# IQ_modulator.net
KiCad netlist of a schematic drawn in Altium Designer
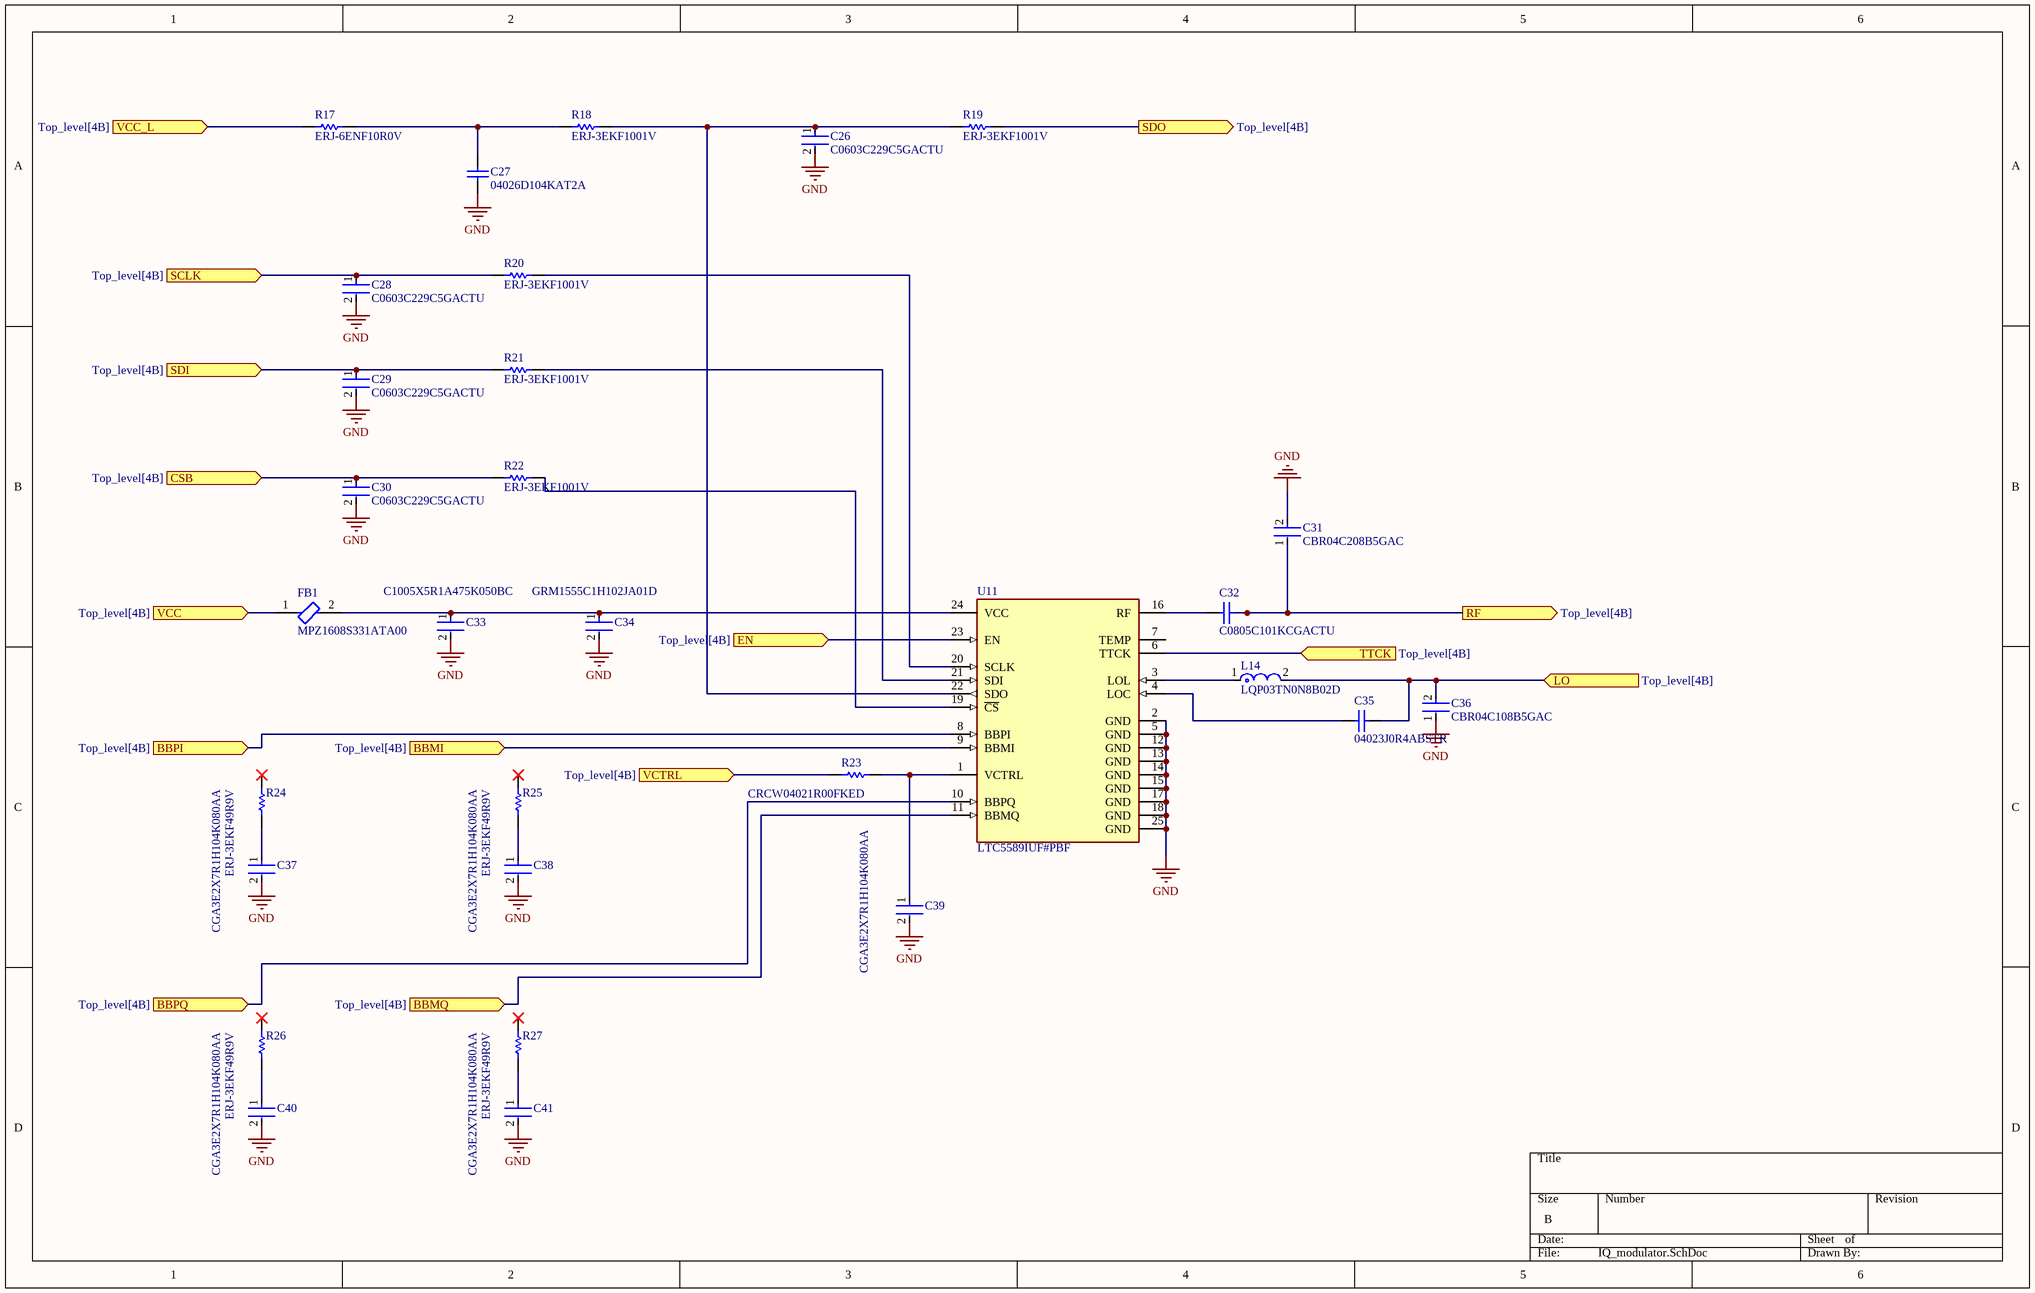
[diagram p0: IQ_modulator.SchDoc]

(export (version "E")
  (design (tool "Eeschema 10.0.6"))
  (components
    (comp (ref "C26")
      (value "C0603C229C5GACTU")
      (footprint "FP-C0603C-CF-MFG")
      (description "CAP CER 2.2PF 50V NP0 0603")
      (fields (field (name "MANUFACTURER") "KEMET") (field (name "TOLERANCE") "0.25 pF"))
      (libsource (lib "Altium Content Vault") (part "b4654b650e69147ec39a6b967a45e02"))
    )
    (comp (ref "C27")
      (value "04026D104KAT2A")
      (footprint "CAPC1005X56X25LL10T15")
      (fields (field (name "MANUFACTURER") "AVX Interconnect / Elco"))
      (libsource (lib "Altium Content Vault") (part "CAP"))
    )
    (comp (ref "C28")
      (value "C0603C229C5GACTU")
      (footprint "FP-C0603C-CF-MFG")
      (description "CAP CER 2.2PF 50V NP0 0603")
      (fields (field (name "MANUFACTURER") "KEMET") (field (name "TOLERANCE") "0.25 pF"))
      (libsource (lib "Altium Content Vault") (part "b4654b650e69147ec39a6b967a45e02"))
    )
    (comp (ref "C29")
      (value "C0603C229C5GACTU")
      (footprint "FP-C0603C-CF-MFG")
      (description "CAP CER 2.2PF 50V NP0 0603")
      (fields (field (name "MANUFACTURER") "KEMET") (field (name "TOLERANCE") "0.25 pF"))
      (libsource (lib "Altium Content Vault") (part "b4654b650e69147ec39a6b967a45e02"))
    )
    (comp (ref "C30")
      (value "C0603C229C5GACTU")
      (footprint "FP-C0603C-CF-MFG")
      (description "CAP CER 2.2PF 50V NP0 0603")
      (fields (field (name "MANUFACTURER") "KEMET") (field (name "TOLERANCE") "0.25 pF"))
      (libsource (lib "Altium Content Vault") (part "b4654b650e69147ec39a6b967a45e02"))
    )
    (comp (ref "C31")
      (value "CBR04C208B5GAC")
      (footprint "FP-CBR04C-MFG")
      (description "CAP CER 0.2PF 50V C0G/NP0 0402")
      (fields (field (name "TOLERANCE") "0.1 pF") (field (name "MANUFACTURER") "KEMET"))
      (libsource (lib "Altium Content Vault") (part "236180d848d6139a670b325ea6854c9"))
    )
    (comp (ref "C32")
      (value "C0805C101KCGACTU")
      (footprint "CAPC2013X140X50NL20T25")
      (fields (field (name "MANUFACTURER") "Kemet"))
      (libsource (lib "Altium Content Vault") (part "CAP"))
    )
    (comp (ref "C33")
      (value "C1005X5R1A475K050BC")
      (footprint "FP-C1005-050-0_15-MFG")
      (description "CAP CER 4.7UF 10V X5R 0402")
      (fields (field (name "TOLERANCE") "10%"))
      (libsource (lib "Altium Content Vault") (part "b4654b650e69147ec39a6b967a45e02"))
    )
    (comp (ref "C34")
      (value "GRM1555C1H102JA01D")
      (footprint "FP-GRM155-0_05-IPC_B")
      (description "Chip Multilayer Ceramic Capacitors for General Purpose, 0402, 1000pF, C0G, 30ppm/°C, 5%, 50V")
      (fields (field (name "TOLERANCE") "5%") (field (name "VOLTAGE") "50V"))
      (libsource (lib "Altium Content Vault") (part "02cd4be3c70576c341d710602a673aa"))
    )
    (comp (ref "C35")
      (value "04023J0R4ABSTR")
      (footprint "CAPC1006X50X20LL10T10")
      (fields (field (name "MANUFACTURER") "AVX Interconnect / Elco"))
      (libsource (lib "Altium Content Vault") (part "CAP"))
    )
    (comp (ref "C36")
      (value "CBR04C108B5GAC")
      (footprint "FP-CBR04C-MFG")
      (description "CAP CER 0.1PF 50V C0G/NP0 0402")
      (fields
        (field (name "OCTOPART") "https://octopart.com/cbr04c108b5gac-kemet-20446735")
        (field (name "TOLERANCE") "0.1 pF")
      )
      (libsource (lib "Altium Content Vault") (part "236180d848d6139a670b325ea6854c9"))
    )
    (comp (ref "C37")
      (value "CGA3E2X7R1H104K080AA")
      (footprint "FP-CGA3E-0_3-0_1-IPC_A")
      (description "Cap Ceramic 100nF 50V X7R 10% Pad SMD 0603 +125°C Automotive T/R")
      (fields (field (name "TOLERANCE") "10%") (field (name "VOLTAGE") "50V"))
      (libsource (lib "Altium Content Vault") (part "b4654b650e69147ec39a6b967a45e02"))
    )
    (comp (ref "C38")
      (value "CGA3E2X7R1H104K080AA")
      (footprint "FP-CGA3E-0_3-0_1-IPC_A")
      (description "Cap Ceramic 100nF 50V X7R 10% Pad SMD 0603 +125°C Automotive T/R")
      (fields (field (name "TOLERANCE") "10%") (field (name "VOLTAGE") "50V"))
      (libsource (lib "Altium Content Vault") (part "b4654b650e69147ec39a6b967a45e02"))
    )
    (comp (ref "C39")
      (value "CGA3E2X7R1H104K080AA")
      (footprint "FP-CGA3E-0_3-0_1-IPC_A")
      (description "Cap Ceramic 100nF 50V X7R 10% Pad SMD 0603 +125°C Automotive T/R")
      (fields (field (name "TOLERANCE") "10%") (field (name "VOLTAGE") "50V"))
      (libsource (lib "Altium Content Vault") (part "b4654b650e69147ec39a6b967a45e02"))
    )
    (comp (ref "C40")
      (value "CGA3E2X7R1H104K080AA")
      (footprint "FP-CGA3E-0_3-0_1-IPC_A")
      (description "Cap Ceramic 100nF 50V X7R 10% Pad SMD 0603 +125°C Automotive T/R")
      (fields (field (name "TOLERANCE") "10%") (field (name "VOLTAGE") "50V"))
      (libsource (lib "Altium Content Vault") (part "b4654b650e69147ec39a6b967a45e02"))
    )
    (comp (ref "C41")
      (value "CGA3E2X7R1H104K080AA")
      (footprint "FP-CGA3E-0_3-0_1-IPC_A")
      (description "Cap Ceramic 100nF 50V X7R 10% Pad SMD 0603 +125°C Automotive T/R")
      (fields (field (name "TOLERANCE") "10%") (field (name "VOLTAGE") "50V"))
      (libsource (lib "Altium Content Vault") (part "b4654b650e69147ec39a6b967a45e02"))
    )
    (comp (ref "FB1")
      (value "MPZ1608S331ATA00")
      (footprint "FP-MPZ1608-0_8-IPC_C")
      (description "Power line Ferrite Bead 330Ω @ 100MHz 1.7A DCR 0.08Ω SMD 0603")
      (fields (field (name "TOLERANCE") "25%"))
      (libsource (lib "Altium Content Vault") (part "5f30dd21d616792df468990f7003faa"))
    )
    (comp (ref "L14")
      (value "LQP03TN0N8B02D")
      (footprint "FP-LQP03TG_02-MFG")
      (description "Film type RF Inductor 0.8nH ±0.1nH 800mA 0.08Ω 0201 (0603)")
      (libsource (lib "Altium Content Vault") (part "4cc4b267dca4c8e51f7102f422741d8"))
    )
    (comp (ref "R17")
      (value "ERJ-6ENF10R0V")
      (footprint "RESC2013X70X40NL20T20")
      (fields (field (name "MANUFACTURER") "Panasonic"))
      (libsource (lib "Altium Content Vault") (part "RES"))
    )
    (comp (ref "R18")
      (value "ERJ-3EKF1001V")
      (footprint "RESC1608X55X30LL15T15")
      (fields (field (name "MANUFACTURER") "Panasonic"))
      (libsource (lib "Altium Content Vault") (part "RES"))
    )
    (comp (ref "R19")
      (value "ERJ-3EKF1001V")
      (footprint "RESC1608X55X30LL15T15")
      (fields (field (name "MANUFACTURER") "Panasonic"))
      (libsource (lib "Altium Content Vault") (part "RES"))
    )
    (comp (ref "R20")
      (value "ERJ-3EKF1001V")
      (footprint "RESC1608X55X30LL15T15")
      (fields (field (name "MANUFACTURER") "Panasonic"))
      (libsource (lib "Altium Content Vault") (part "RES"))
    )
    (comp (ref "R21")
      (value "ERJ-3EKF1001V")
      (footprint "RESC1608X55X30LL15T15")
      (fields (field (name "MANUFACTURER") "Panasonic"))
      (libsource (lib "Altium Content Vault") (part "RES"))
    )
    (comp (ref "R22")
      (value "ERJ-3EKF1001V")
      (footprint "RESC1608X55X30LL15T15")
      (fields (field (name "MANUFACTURER") "Panasonic"))
      (libsource (lib "Altium Content Vault") (part "RES"))
    )
    (comp (ref "R23")
      (value "CRCW04021R00FKED")
      (footprint "RESC1005X40X25ML05T05")
      (fields (field (name "MANUFACTURER") "Vishay Dale"))
      (libsource (lib "Altium Content Vault") (part "RES"))
    )
    (comp (ref "R24")
      (value "ERJ-3EKF49R9V")
      (footprint "RESC1608X55X30ML15T15")
      (fields (field (name "MANUFACTURER") "Panasonic"))
      (libsource (lib "Altium Content Vault") (part "RES"))
    )
    (comp (ref "R25")
      (value "ERJ-3EKF49R9V")
      (footprint "RESC1608X55X30ML15T15")
      (fields (field (name "MANUFACTURER") "Panasonic"))
      (libsource (lib "Altium Content Vault") (part "RES"))
    )
    (comp (ref "R26")
      (value "ERJ-3EKF49R9V")
      (footprint "RESC1608X55X30ML15T15")
      (fields (field (name "MANUFACTURER") "Panasonic"))
      (libsource (lib "Altium Content Vault") (part "RES"))
    )
    (comp (ref "R27")
      (value "ERJ-3EKF49R9V")
      (footprint "RESC1608X55X30ML15T15")
      (fields (field (name "MANUFACTURER") "Panasonic"))
      (libsource (lib "Altium Content Vault") (part "RES"))
    )
    (comp (ref "U11")
      (value "LTC5589IUF#PBF")
      (footprint "FP-UF-24-05-08-1697-MFG")
      (description "RF MODULATOR 700MHZ-6GHZ 24WFQFN")
      (libsource (lib "Altium Content Vault") (part "19ce8fc1515bfbc9ccbb626fa706872"))
    )
  )
  (nets
    (net (code "1") (name "/BBMI") (class "Default")
      (node (ref "U11") (pin "9") (pinfunction "BBMI_9") (pintype "input"))
    )
    (net (code "2") (name "/BBMQ") (class "Default")
      (node (ref "U11") (pin "11") (pinfunction "BBMQ_11") (pintype "input"))
    )
    (net (code "3") (name "/BBPI") (class "Default")
      (node (ref "U11") (pin "8") (pinfunction "BBPI_8") (pintype "input"))
    )
    (net (code "4") (name "/BBPQ") (class "Default")
      (node (ref "U11") (pin "10") (pinfunction "BBPQ_10") (pintype "input"))
    )
    (net (code "5") (name "/CSB") (class "Default")
      (node (ref "C30") (pin "1") (pinfunction "1_1") (pintype "passive"))
      (node (ref "R22") (pin "1") (pinfunction "1_1") (pintype "passive"))
    )
    (net (code "6") (name "/EN") (class "Default")
      (node (ref "U11") (pin "23") (pinfunction "EN_23") (pintype "input"))
    )
    (net (code "7") (name "/LO") (class "Default")
      (node (ref "C35") (pin "2") (pinfunction "2_2") (pintype "passive"))
      (node (ref "C36") (pin "2") (pinfunction "2_2") (pintype "passive"))
      (node (ref "L14") (pin "2") (pinfunction "2_2") (pintype "passive"))
    )
    (net (code "8") (name "/RF") (class "Default")
      (node (ref "C31") (pin "1") (pinfunction "1_1") (pintype "passive"))
      (node (ref "C32") (pin "2") (pinfunction "2_2") (pintype "passive"))
    )
    (net (code "9") (name "/SCLK") (class "Default")
      (node (ref "C28") (pin "1") (pinfunction "1_1") (pintype "passive"))
      (node (ref "R20") (pin "1") (pinfunction "1_1") (pintype "passive"))
    )
    (net (code "10") (name "/SDI") (class "Default")
      (node (ref "C29") (pin "1") (pinfunction "1_1") (pintype "passive"))
      (node (ref "R21") (pin "1") (pinfunction "1_1") (pintype "passive"))
    )
    (net (code "11") (name "/SDO") (class "Default")
      (node (ref "R19") (pin "2") (pinfunction "2_2") (pintype "passive"))
    )
    (net (code "12") (name "/TTCK") (class "Default")
      (node (ref "U11") (pin "6") (pinfunction "TTCK_6") (pintype "passive"))
    )
    (net (code "13") (name "/VCC") (class "Default")
      (node (ref "FB1") (pin "1") (pinfunction "1_1") (pintype "passive"))
    )
    (net (code "14") (name "/VCC_L") (class "Default")
      (node (ref "R17") (pin "1") (pinfunction "1_1") (pintype "passive"))
    )
    (net (code "15") (name "/VCTRL") (class "Default")
      (node (ref "R23") (pin "1") (pinfunction "1_1") (pintype "passive"))
    )
    (net (code "16") (name "GND") (class "Default")
      (node (ref "C26") (pin "2") (pinfunction "2_2") (pintype "passive"))
      (node (ref "C27") (pin "1") (pinfunction "1_1") (pintype "passive"))
      (node (ref "C28") (pin "2") (pinfunction "2_2") (pintype "passive"))
      (node (ref "C29") (pin "2") (pinfunction "2_2") (pintype "passive"))
      (node (ref "C30") (pin "2") (pinfunction "2_2") (pintype "passive"))
      (node (ref "C31") (pin "2") (pinfunction "2_2") (pintype "passive"))
      (node (ref "C33") (pin "2") (pinfunction "2_2") (pintype "passive"))
      (node (ref "C34") (pin "2") (pinfunction "2_2") (pintype "passive"))
      (node (ref "C36") (pin "1") (pinfunction "1_1") (pintype "passive"))
      (node (ref "C37") (pin "2") (pinfunction "2_2") (pintype "passive"))
      (node (ref "C38") (pin "2") (pinfunction "2_2") (pintype "passive"))
      (node (ref "C39") (pin "2") (pinfunction "2_2") (pintype "passive"))
      (node (ref "C40") (pin "2") (pinfunction "2_2") (pintype "passive"))
      (node (ref "C41") (pin "2") (pinfunction "2_2") (pintype "passive"))
      (node (ref "U11") (pin "12") (pinfunction "GND_12") (pintype "power_in"))
      (node (ref "U11") (pin "13") (pinfunction "GND_13") (pintype "power_in"))
      (node (ref "U11") (pin "14") (pinfunction "GND_14") (pintype "power_in"))
      (node (ref "U11") (pin "15") (pinfunction "GND_15") (pintype "power_in"))
      (node (ref "U11") (pin "17") (pinfunction "GND_17") (pintype "power_in"))
      (node (ref "U11") (pin "18") (pinfunction "GND_18") (pintype "power_in"))
      (node (ref "U11") (pin "2") (pinfunction "GND_2") (pintype "power_in"))
      (node (ref "U11") (pin "25") (pinfunction "GND_25") (pintype "power_in"))
      (node (ref "U11") (pin "5") (pinfunction "GND_5") (pintype "power_in"))
    )
    (net (code "17") (name "Net-(C27-Pad2)") (class "Default")
      (node (ref "C27") (pin "2") (pinfunction "2_2") (pintype "passive"))
      (node (ref "R17") (pin "2") (pinfunction "2_2") (pintype "passive"))
      (node (ref "R18") (pin "1") (pinfunction "1_1") (pintype "passive"))
    )
    (net (code "18") (name "Net-(C37-Pad1)") (class "Default")
      (node (ref "C37") (pin "1") (pinfunction "1_1") (pintype "passive"))
      (node (ref "R24") (pin "1") (pinfunction "1_1") (pintype "passive"))
    )
    (net (code "19") (name "Net-(C38-Pad1)") (class "Default")
      (node (ref "C38") (pin "1") (pinfunction "1_1") (pintype "passive"))
      (node (ref "R25") (pin "1") (pinfunction "1_1") (pintype "passive"))
    )
    (net (code "20") (name "Net-(C40-Pad1)") (class "Default")
      (node (ref "C40") (pin "1") (pinfunction "1_1") (pintype "passive"))
      (node (ref "R26") (pin "1") (pinfunction "1_1") (pintype "passive"))
    )
    (net (code "21") (name "Net-(C41-Pad1)") (class "Default")
      (node (ref "C41") (pin "1") (pinfunction "1_1") (pintype "passive"))
      (node (ref "R27") (pin "1") (pinfunction "1_1") (pintype "passive"))
    )
    (net (code "22") (name "Net-(U11-LOC)") (class "Default")
      (node (ref "C35") (pin "1") (pinfunction "1_1") (pintype "passive"))
      (node (ref "U11") (pin "4") (pinfunction "LOC_4") (pintype "input"))
    )
    (net (code "23") (name "Net-(U11-LOL)") (class "Default")
      (node (ref "L14") (pin "1") (pinfunction "1_1") (pintype "passive"))
      (node (ref "U11") (pin "3") (pinfunction "LOL_3") (pintype "input"))
    )
    (net (code "24") (name "Net-(U11-RF)") (class "Default")
      (node (ref "C32") (pin "1") (pinfunction "1_1") (pintype "passive"))
      (node (ref "U11") (pin "16") (pinfunction "RF_16") (pintype "passive"))
    )
    (net (code "25") (name "Net-(U11-SCLK)") (class "Default")
      (node (ref "R20") (pin "2") (pinfunction "2_2") (pintype "passive"))
      (node (ref "U11") (pin "20") (pinfunction "SCLK_20") (pintype "input"))
    )
    (net (code "26") (name "Net-(U11-SDI)") (class "Default")
      (node (ref "R21") (pin "2") (pinfunction "2_2") (pintype "passive"))
      (node (ref "U11") (pin "21") (pinfunction "SDI_21") (pintype "input"))
    )
    (net (code "27") (name "Net-(U11-SDO)") (class "Default")
      (node (ref "C26") (pin "1") (pinfunction "1_1") (pintype "passive"))
      (node (ref "R18") (pin "2") (pinfunction "2_2") (pintype "passive"))
      (node (ref "R19") (pin "1") (pinfunction "1_1") (pintype "passive"))
      (node (ref "U11") (pin "22") (pinfunction "SDO_22") (pintype "output"))
    )
    (net (code "28") (name "Net-(U11-VCC)") (class "Default")
      (node (ref "C33") (pin "1") (pinfunction "1_1") (pintype "passive"))
      (node (ref "C34") (pin "1") (pinfunction "1_1") (pintype "passive"))
      (node (ref "FB1") (pin "2") (pinfunction "2_2") (pintype "passive"))
      (node (ref "U11") (pin "24") (pinfunction "VCC_24") (pintype "power_in"))
    )
    (net (code "29") (name "Net-(U11-VCTRL)") (class "Default")
      (node (ref "C39") (pin "1") (pinfunction "1_1") (pintype "passive"))
      (node (ref "R23") (pin "2") (pinfunction "2_2") (pintype "passive"))
      (node (ref "U11") (pin "1") (pinfunction "VCTRL_1") (pintype "passive"))
    )
    (net (code "30") (name "Net-(U11-~{CS})") (class "Default")
      (node (ref "R22") (pin "2") (pinfunction "2_2") (pintype "passive"))
      (node (ref "U11") (pin "19") (pinfunction "~{CS}_19") (pintype "input"))
    )
    (net (code "31") (name "unconnected-(R24-Pad2)") (class "Default")
      (node (ref "R24") (pin "2") (pinfunction "2_2") (pintype "passive+no_connect"))
    )
    (net (code "32") (name "unconnected-(R25-Pad2)") (class "Default")
      (node (ref "R25") (pin "2") (pinfunction "2_2") (pintype "passive+no_connect"))
    )
    (net (code "33") (name "unconnected-(R26-Pad2)") (class "Default")
      (node (ref "R26") (pin "2") (pinfunction "2_2") (pintype "passive+no_connect"))
    )
    (net (code "34") (name "unconnected-(R27-Pad2)") (class "Default")
      (node (ref "R27") (pin "2") (pinfunction "2_2") (pintype "passive+no_connect"))
    )
    (net (code "35") (name "unconnected-(U11-TEMP-Pad7)") (class "Default")
      (node (ref "U11") (pin "7") (pinfunction "TEMP_7") (pintype "passive"))
    )
  )
)
